# Flight_Controller_board.net
KiCad netlist of a schematic drawn in EAGLE
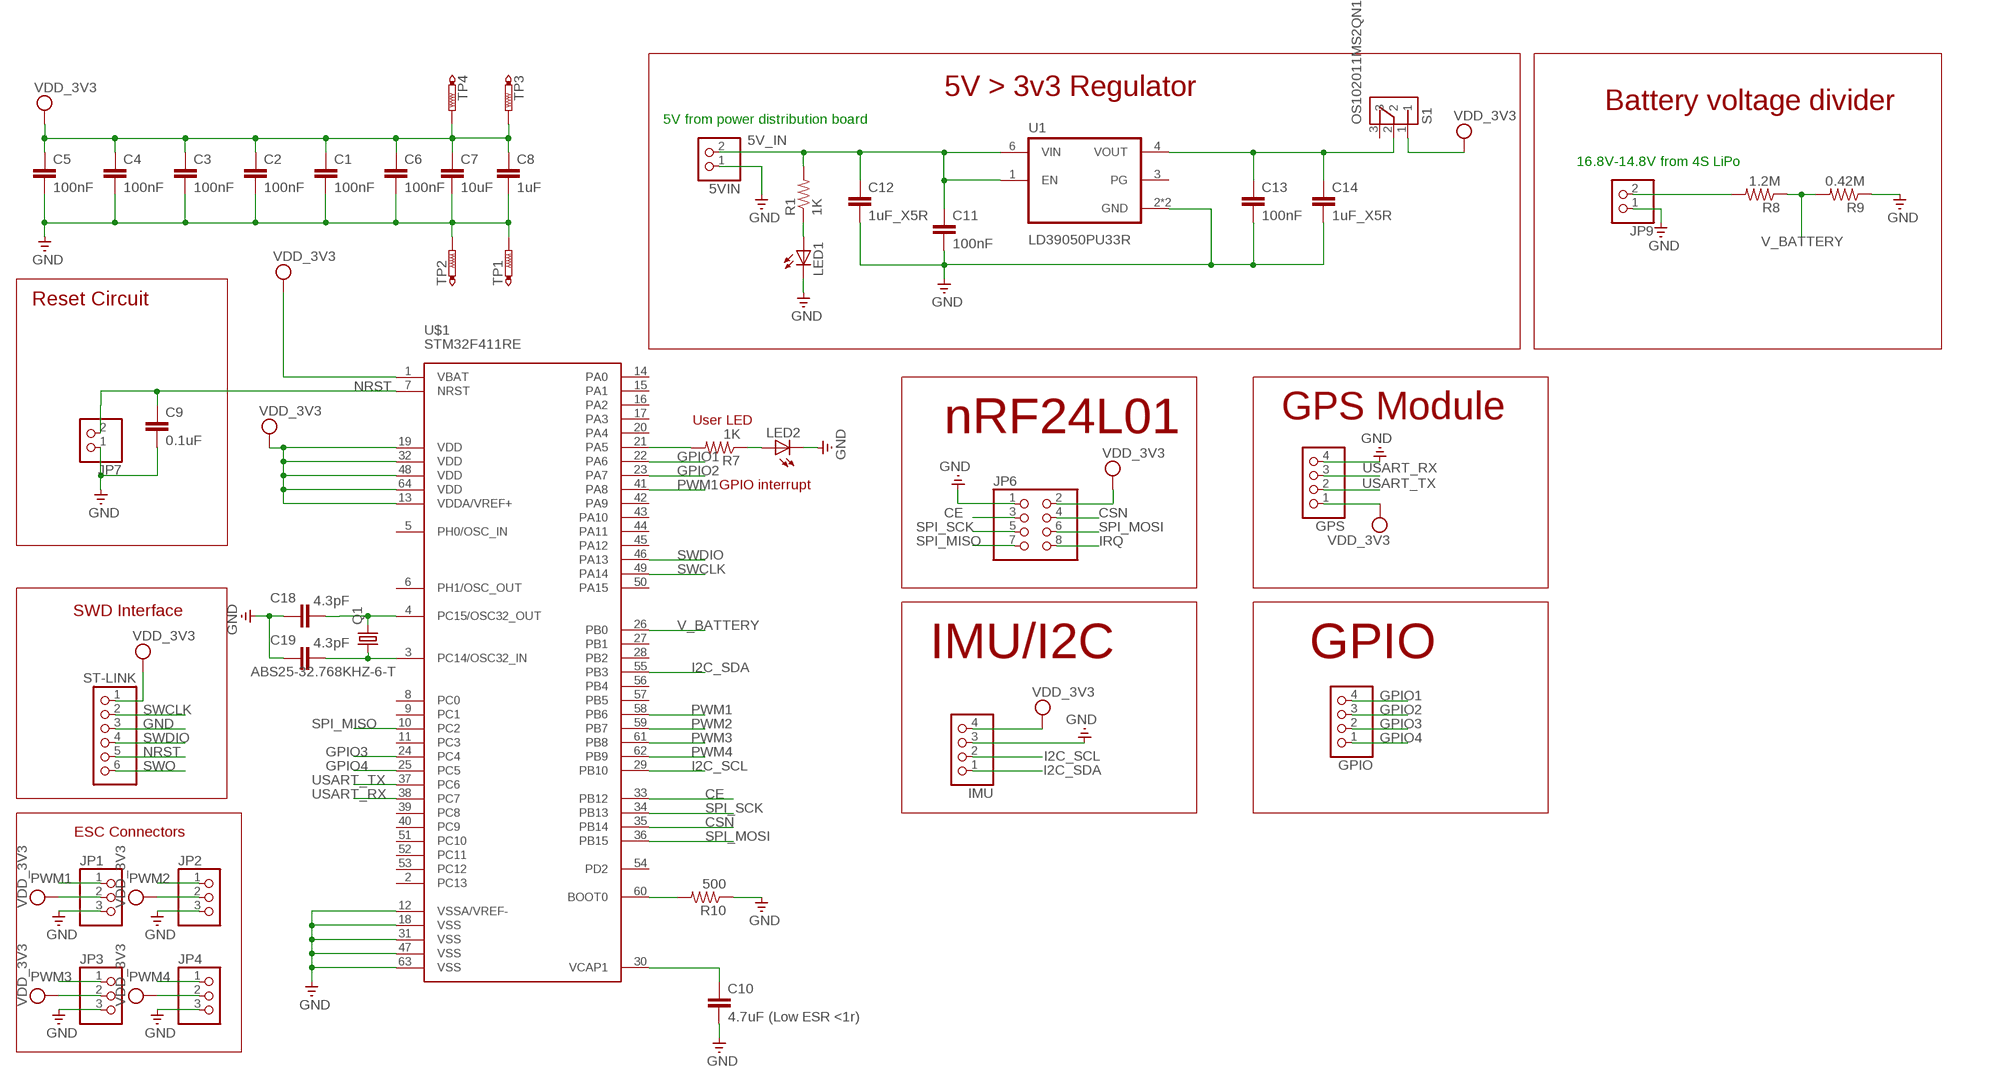
[diagram p0: schematic, sheet 1]

(export (version "E")
  (design (tool "Eeschema 10.0.6"))
  (components
    (comp (ref "5VIN")
      (value "PINHD-1X2")
      (footprint "eagle-import:1X02")
      (libsource (lib "eagle-import") (part "PINHD-1X2"))
    )
    (comp (ref "C1")
      (value "100nF")
      (footprint "eagle-import:0603-CAP")
      (libsource (lib "eagle-import") (part "CAP0603-CAP"))
    )
    (comp (ref "C2")
      (value "100nF")
      (footprint "eagle-import:0603-CAP")
      (libsource (lib "eagle-import") (part "CAP0603-CAP"))
    )
    (comp (ref "C3")
      (value "100nF")
      (footprint "eagle-import:0603-CAP")
      (libsource (lib "eagle-import") (part "CAP0603-CAP"))
    )
    (comp (ref "C4")
      (value "100nF")
      (footprint "eagle-import:0603-CAP")
      (libsource (lib "eagle-import") (part "CAP0603-CAP"))
    )
    (comp (ref "C5")
      (value "100nF")
      (footprint "eagle-import:0603-CAP")
      (libsource (lib "eagle-import") (part "CAP0603-CAP"))
    )
    (comp (ref "C6")
      (value "100nF")
      (footprint "eagle-import:0603-CAP")
      (libsource (lib "eagle-import") (part "CAP0603-CAP"))
    )
    (comp (ref "C7")
      (value "10uF")
      (footprint "eagle-import:0603-CAP")
      (libsource (lib "eagle-import") (part "CAP0603-CAP"))
    )
    (comp (ref "C8")
      (value "1uF")
      (footprint "eagle-import:0603-CAP")
      (libsource (lib "eagle-import") (part "CAP0603-CAP"))
    )
    (comp (ref "C9")
      (value "0.1uF")
      (footprint "eagle-import:0603-CAP")
      (libsource (lib "eagle-import") (part "CAP0603-CAP"))
    )
    (comp (ref "C10")
      (value "4.7uF (Low ESR <1r)")
      (footprint "eagle-import:1210")
      (libsource (lib "eagle-import") (part "CAP1210"))
    )
    (comp (ref "C11")
      (value "100nF")
      (footprint "eagle-import:0603-CAP")
      (libsource (lib "eagle-import") (part "CAP0603-CAP"))
    )
    (comp (ref "C12")
      (value "1uF_X5R")
      (footprint "eagle-import:0603-CAP")
      (libsource (lib "eagle-import") (part "CAP0603-CAP"))
    )
    (comp (ref "C13")
      (value "100nF")
      (footprint "eagle-import:0603-CAP")
      (libsource (lib "eagle-import") (part "CAP0603-CAP"))
    )
    (comp (ref "C14")
      (value "1uF_X5R")
      (footprint "eagle-import:0603-CAP")
      (libsource (lib "eagle-import") (part "CAP0603-CAP"))
    )
    (comp (ref "C18")
      (value "4.3pF")
      (footprint "eagle-import:0603-CAP")
      (libsource (lib "eagle-import") (part "CAP0603-CAP"))
    )
    (comp (ref "C19")
      (value "4.3pF")
      (footprint "eagle-import:0603-CAP")
      (libsource (lib "eagle-import") (part "CAP0603-CAP"))
    )
    (comp (ref "GPIO")
      (value "PINHD-1X4")
      (footprint "eagle-import:1X04")
      (libsource (lib "eagle-import") (part "PINHD-1X4"))
    )
    (comp (ref "GPS")
      (value "PINHD-1X4")
      (footprint "eagle-import:1X04")
      (libsource (lib "eagle-import") (part "PINHD-1X4"))
    )
    (comp (ref "IMU")
      (value "PINHD-1X4")
      (footprint "eagle-import:1X04")
      (libsource (lib "eagle-import") (part "PINHD-1X4"))
    )
    (comp (ref "JP1")
      (value "PINHD-1X3")
      (footprint "eagle-import:1X03")
      (libsource (lib "eagle-import") (part "PINHD-1X3"))
    )
    (comp (ref "JP2")
      (value "PINHD-1X3")
      (footprint "eagle-import:1X03")
      (libsource (lib "eagle-import") (part "PINHD-1X3"))
    )
    (comp (ref "JP3")
      (value "PINHD-1X3")
      (footprint "eagle-import:1X03")
      (libsource (lib "eagle-import") (part "PINHD-1X3"))
    )
    (comp (ref "JP4")
      (value "PINHD-1X3")
      (footprint "eagle-import:1X03")
      (libsource (lib "eagle-import") (part "PINHD-1X3"))
    )
    (comp (ref "JP6")
      (value "PINHD-2X4")
      (footprint "eagle-import:2X04")
      (libsource (lib "eagle-import") (part "PINHD-2X4"))
    )
    (comp (ref "JP7")
      (value "PINHD-1X2")
      (footprint "eagle-import:1X02")
      (libsource (lib "eagle-import") (part "PINHD-1X2"))
    )
    (comp (ref "JP9")
      (value "PINHD-1X2")
      (footprint "eagle-import:1X02")
      (libsource (lib "eagle-import") (part "PINHD-1X2"))
    )
    (comp (ref "LED1")
      (value "LEDCHIPLED_0603")
      (footprint "eagle-import:CHIPLED_0603")
      (libsource (lib "eagle-import") (part "LEDCHIPLED_0603"))
    )
    (comp (ref "LED2")
      (value "LEDCHIPLED_0603")
      (footprint "eagle-import:CHIPLED_0603")
      (libsource (lib "eagle-import") (part "LEDCHIPLED_0603"))
    )
    (comp (ref "Q1")
      (value "ABS25-32.768KHZ-6-T")
      (footprint "eagle-import:MC-306")
      (fields (field (name "MPN") "MC-306 60.0KHZ  100PPM ,12.5PF"))
      (libsource (lib "eagle-import") (part "MC-306"))
    )
    (comp (ref "R1")
      (value "1K")
      (footprint "eagle-import:0603-RES")
      (libsource (lib "eagle-import") (part "RESISTOR0603-RES"))
    )
    (comp (ref "R7")
      (value "1K")
      (footprint "eagle-import:0603-RES")
      (libsource (lib "eagle-import") (part "RESISTOR0603-RES"))
    )
    (comp (ref "R8")
      (value "1.2M")
      (footprint "eagle-import:0603-RES")
      (libsource (lib "eagle-import") (part "RESISTOR0603-RES"))
    )
    (comp (ref "R9")
      (value "0.42M")
      (footprint "eagle-import:0603-RES")
      (libsource (lib "eagle-import") (part "RESISTOR0603-RES"))
    )
    (comp (ref "R10")
      (value "500")
      (footprint "eagle-import:0603-RES")
      (libsource (lib "eagle-import") (part "RESISTOR0603-RES"))
    )
    (comp (ref "S1")
      (value "OS102011MS2QN1")
      (footprint "eagle-import:SW_OS102011MS2QN1")
      (fields (field (name "MF") "C&K"))
      (libsource (lib "eagle-import") (part "OS102011MS2QN1"))
    )
    (comp (ref "ST-LINK")
      (value "PINHD-1X6")
      (footprint "eagle-import:1X06")
      (libsource (lib "eagle-import") (part "PINHD-1X6"))
    )
    (comp (ref "TP1")
      (value "PTR1B1,27")
      (footprint "eagle-import:B1,27")
      (libsource (lib "eagle-import") (part "PTR1B1,27"))
    )
    (comp (ref "TP2")
      (value "PTR1B1,27")
      (footprint "eagle-import:B1,27")
      (libsource (lib "eagle-import") (part "PTR1B1,27"))
    )
    (comp (ref "TP3")
      (value "PTR1B1,27")
      (footprint "eagle-import:B1,27")
      (libsource (lib "eagle-import") (part "PTR1B1,27"))
    )
    (comp (ref "TP4")
      (value "PTR1B1,27")
      (footprint "eagle-import:B1,27")
      (libsource (lib "eagle-import") (part "PTR1B1,27"))
    )
    (comp (ref "U$1")
      (value "STM32F411RE")
      (footprint "eagle-import:LQFP64")
      (libsource (lib "eagle-import") (part "STM32F411XC"))
    )
    (comp (ref "U1")
      (value "LD39050PU33R")
      (footprint "eagle-import:SON95P300X300X100-7N")
      (fields (field (name "MF") "STMicroelectronics"))
      (libsource (lib "eagle-import") (part "LD39050PU33R"))
    )
  )
  (nets
    (net (code "1") (name "/5V_IN") (class "Default")
      (node (ref "5VIN") (pin "2") (pinfunction "2_2") (pintype "passive"))
      (node (ref "C11") (pin "1") (pinfunction "1_1") (pintype "passive"))
      (node (ref "C12") (pin "1") (pinfunction "1_1") (pintype "passive"))
      (node (ref "R1") (pin "2") (pinfunction "2_2") (pintype "passive"))
      (node (ref "U1") (pin "1") (pinfunction "EN_1") (pintype "input"))
      (node (ref "U1") (pin "6") (pinfunction "VIN_6") (pintype "power_in"))
    )
    (net (code "2") (name "/CE") (class "Default")
      (node (ref "JP6") (pin "3") (pinfunction "3_3") (pintype "passive"))
      (node (ref "U$1") (pin "33") (pinfunction "PB12_33") (pintype "bidirectional"))
    )
    (net (code "3") (name "/CSN") (class "Default")
      (node (ref "JP6") (pin "4") (pinfunction "4_4") (pintype "passive"))
      (node (ref "U$1") (pin "35") (pinfunction "PB14_35") (pintype "bidirectional"))
    )
    (net (code "4") (name "/GPIO1") (class "Default")
      (node (ref "GPIO") (pin "4") (pinfunction "4_4") (pintype "passive"))
      (node (ref "U$1") (pin "22") (pinfunction "PA6_22") (pintype "bidirectional"))
    )
    (net (code "5") (name "/GPIO2") (class "Default")
      (node (ref "GPIO") (pin "3") (pinfunction "3_3") (pintype "passive"))
      (node (ref "U$1") (pin "23") (pinfunction "PA7_23") (pintype "bidirectional"))
    )
    (net (code "6") (name "/GPIO3") (class "Default")
      (node (ref "GPIO") (pin "2") (pinfunction "2_2") (pintype "passive"))
      (node (ref "U$1") (pin "24") (pinfunction "PC4_24") (pintype "bidirectional"))
    )
    (net (code "7") (name "/GPIO4") (class "Default")
      (node (ref "GPIO") (pin "1") (pinfunction "1_1") (pintype "passive"))
      (node (ref "U$1") (pin "25") (pinfunction "PC5_25") (pintype "bidirectional"))
    )
    (net (code "8") (name "/I2C_SCL") (class "Default")
      (node (ref "IMU") (pin "2") (pinfunction "2_2") (pintype "passive"))
      (node (ref "U$1") (pin "29") (pinfunction "PB10_29") (pintype "bidirectional"))
    )
    (net (code "9") (name "/I2C_SDA") (class "Default")
      (node (ref "IMU") (pin "1") (pinfunction "1_1") (pintype "passive"))
      (node (ref "U$1") (pin "55") (pinfunction "PB3_55") (pintype "bidirectional"))
    )
    (net (code "10") (name "/IRQ") (class "Default")
      (node (ref "JP6") (pin "8") (pinfunction "8_8") (pintype "passive"))
    )
    (net (code "11") (name "/NRST") (class "Default")
      (node (ref "C9") (pin "1") (pinfunction "1_1") (pintype "passive"))
      (node (ref "JP7") (pin "2") (pinfunction "2_2") (pintype "passive"))
      (node (ref "ST-LINK") (pin "5") (pinfunction "5_5") (pintype "passive"))
      (node (ref "U$1") (pin "7") (pinfunction "NRST_7") (pintype "bidirectional"))
    )
    (net (code "12") (name "/PWM1") (class "Default")
      (node (ref "JP1") (pin "1") (pinfunction "1_1") (pintype "passive"))
      (node (ref "U$1") (pin "41") (pinfunction "PA8_41") (pintype "bidirectional"))
      (node (ref "U$1") (pin "58") (pinfunction "PB6_58") (pintype "bidirectional"))
    )
    (net (code "13") (name "/PWM2") (class "Default")
      (node (ref "JP2") (pin "1") (pinfunction "1_1") (pintype "passive"))
      (node (ref "U$1") (pin "59") (pinfunction "PB7_59") (pintype "bidirectional"))
    )
    (net (code "14") (name "/PWM3") (class "Default")
      (node (ref "JP3") (pin "1") (pinfunction "1_1") (pintype "passive"))
      (node (ref "U$1") (pin "61") (pinfunction "PB8_61") (pintype "bidirectional"))
    )
    (net (code "15") (name "/PWM4") (class "Default")
      (node (ref "JP4") (pin "1") (pinfunction "1_1") (pintype "passive"))
      (node (ref "U$1") (pin "62") (pinfunction "PB9_62") (pintype "bidirectional"))
    )
    (net (code "16") (name "/SPI_MISO") (class "Default")
      (node (ref "JP6") (pin "7") (pinfunction "7_7") (pintype "passive"))
      (node (ref "U$1") (pin "10") (pinfunction "PC2_10") (pintype "bidirectional"))
    )
    (net (code "17") (name "/SPI_MOSI") (class "Default")
      (node (ref "JP6") (pin "6") (pinfunction "6_6") (pintype "passive"))
      (node (ref "U$1") (pin "36") (pinfunction "PB15_36") (pintype "bidirectional"))
    )
    (net (code "18") (name "/SPI_SCK") (class "Default")
      (node (ref "JP6") (pin "5") (pinfunction "5_5") (pintype "passive"))
      (node (ref "U$1") (pin "34") (pinfunction "PB13_34") (pintype "bidirectional"))
    )
    (net (code "19") (name "/SWCLK") (class "Default")
      (node (ref "ST-LINK") (pin "2") (pinfunction "2_2") (pintype "passive"))
      (node (ref "U$1") (pin "49") (pinfunction "PA14_49") (pintype "bidirectional"))
    )
    (net (code "20") (name "/SWDIO") (class "Default")
      (node (ref "ST-LINK") (pin "4") (pinfunction "4_4") (pintype "passive"))
      (node (ref "U$1") (pin "46") (pinfunction "PA13_46") (pintype "bidirectional"))
    )
    (net (code "21") (name "/SWO") (class "Default")
      (node (ref "ST-LINK") (pin "6") (pinfunction "6_6") (pintype "passive"))
    )
    (net (code "22") (name "/USART_RX") (class "Default")
      (node (ref "GPS") (pin "3") (pinfunction "3_3") (pintype "passive"))
      (node (ref "U$1") (pin "38") (pinfunction "PC7_38") (pintype "bidirectional"))
    )
    (net (code "23") (name "/USART_TX") (class "Default")
      (node (ref "GPS") (pin "2") (pinfunction "2_2") (pintype "passive"))
      (node (ref "U$1") (pin "37") (pinfunction "PC6_37") (pintype "bidirectional"))
    )
    (net (code "24") (name "/V_BATTERY") (class "Default")
      (node (ref "R8") (pin "1") (pinfunction "1_1") (pintype "passive"))
      (node (ref "R9") (pin "2") (pinfunction "2_2") (pintype "passive"))
      (node (ref "U$1") (pin "26") (pinfunction "PB0_26") (pintype "bidirectional"))
    )
    (net (code "25") (name "GND") (class "Default")
      (node (ref "5VIN") (pin "1") (pinfunction "1_1") (pintype "passive"))
      (node (ref "C1") (pin "2") (pinfunction "2_2") (pintype "passive"))
      (node (ref "C10") (pin "2") (pinfunction "2_2") (pintype "passive"))
      (node (ref "C11") (pin "2") (pinfunction "2_2") (pintype "passive"))
      (node (ref "C12") (pin "2") (pinfunction "2_2") (pintype "passive"))
      (node (ref "C13") (pin "2") (pinfunction "2_2") (pintype "passive"))
      (node (ref "C14") (pin "2") (pinfunction "2_2") (pintype "passive"))
      (node (ref "C18") (pin "1") (pinfunction "1_1") (pintype "passive"))
      (node (ref "C19") (pin "1") (pinfunction "1_1") (pintype "passive"))
      (node (ref "C2") (pin "2") (pinfunction "2_2") (pintype "passive"))
      (node (ref "C3") (pin "2") (pinfunction "2_2") (pintype "passive"))
      (node (ref "C4") (pin "2") (pinfunction "2_2") (pintype "passive"))
      (node (ref "C5") (pin "2") (pinfunction "2_2") (pintype "passive"))
      (node (ref "C6") (pin "2") (pinfunction "2_2") (pintype "passive"))
      (node (ref "C7") (pin "2") (pinfunction "2_2") (pintype "passive"))
      (node (ref "C8") (pin "2") (pinfunction "2_2") (pintype "passive"))
      (node (ref "C9") (pin "2") (pinfunction "2_2") (pintype "passive"))
      (node (ref "GPS") (pin "4") (pinfunction "4_4") (pintype "passive"))
      (node (ref "IMU") (pin "3") (pinfunction "3_3") (pintype "passive"))
      (node (ref "JP1") (pin "3") (pinfunction "3_3") (pintype "passive"))
      (node (ref "JP2") (pin "3") (pinfunction "3_3") (pintype "passive"))
      (node (ref "JP3") (pin "3") (pinfunction "3_3") (pintype "passive"))
      (node (ref "JP4") (pin "3") (pinfunction "3_3") (pintype "passive"))
      (node (ref "JP6") (pin "1") (pinfunction "1_1") (pintype "passive"))
      (node (ref "JP7") (pin "1") (pinfunction "1_1") (pintype "passive"))
      (node (ref "JP9") (pin "1") (pinfunction "1_1") (pintype "passive"))
      (node (ref "LED1") (pin "C") (pinfunction "C_C") (pintype "passive"))
      (node (ref "LED2") (pin "C") (pinfunction "C_C") (pintype "passive"))
      (node (ref "R10") (pin "1") (pinfunction "1_1") (pintype "passive"))
      (node (ref "R9") (pin "1") (pinfunction "1_1") (pintype "passive"))
      (node (ref "ST-LINK") (pin "3") (pinfunction "3_3") (pintype "passive"))
      (node (ref "TP1") (pin "TP") (pinfunction "TP_TP") (pintype "input"))
      (node (ref "TP2") (pin "TP") (pinfunction "TP_TP") (pintype "input"))
      (node (ref "U$1") (pin "12") (pinfunction "VSSA/VREF-_12") (pintype "bidirectional"))
      (node (ref "U$1") (pin "18") (pinfunction "VSS_18") (pintype "bidirectional"))
      (node (ref "U$1") (pin "31") (pinfunction "VSS_31") (pintype "bidirectional"))
      (node (ref "U$1") (pin "47") (pinfunction "VSS_47") (pintype "bidirectional"))
      (node (ref "U$1") (pin "63") (pinfunction "VSS_63") (pintype "bidirectional"))
      (node (ref "U1") (pin "2") (pinfunction "GND_2") (pintype "power_in"))
      (node (ref "U1") (pin "7") (pinfunction "GND_7") (pintype "power_in"))
    )
    (net (code "26") (name "Net-(JP9-Pad2)") (class "Default")
      (node (ref "JP9") (pin "2") (pinfunction "2_2") (pintype "passive"))
      (node (ref "R8") (pin "2") (pinfunction "2_2") (pintype "passive"))
    )
    (net (code "27") (name "Net-(LED1-PadA)") (class "Default")
      (node (ref "LED1") (pin "A") (pinfunction "A_A") (pintype "passive"))
      (node (ref "R1") (pin "1") (pinfunction "1_1") (pintype "passive"))
    )
    (net (code "28") (name "Net-(LED2-PadA)") (class "Default")
      (node (ref "LED2") (pin "A") (pinfunction "A_A") (pintype "passive"))
      (node (ref "R7") (pin "1") (pinfunction "1_1") (pintype "passive"))
    )
    (net (code "29") (name "Net-(Q1-2)") (class "Default")
      (node (ref "C18") (pin "2") (pinfunction "2_2") (pintype "passive"))
      (node (ref "Q1") (pin "4") (pinfunction "2_4") (pintype "passive"))
      (node (ref "U$1") (pin "4") (pinfunction "PC15/OSC32_OUT_4") (pintype "bidirectional"))
    )
    (net (code "30") (name "Net-(U$1-BOOT0)") (class "Default")
      (node (ref "R10") (pin "2") (pinfunction "2_2") (pintype "passive"))
      (node (ref "U$1") (pin "60") (pinfunction "BOOT0_60") (pintype "bidirectional"))
    )
    (net (code "31") (name "Net-(U$1-PA5)") (class "Default")
      (node (ref "R7") (pin "2") (pinfunction "2_2") (pintype "passive"))
      (node (ref "U$1") (pin "21") (pinfunction "PA5_21") (pintype "bidirectional"))
    )
    (net (code "32") (name "Net-(U$1-PC14{slash}OSC32_IN)") (class "Default")
      (node (ref "C19") (pin "2") (pinfunction "2_2") (pintype "passive"))
      (node (ref "Q1") (pin "1") (pinfunction "1_1") (pintype "passive"))
      (node (ref "U$1") (pin "3") (pinfunction "PC14/OSC32_IN_3") (pintype "bidirectional"))
    )
    (net (code "33") (name "Net-(U$1-VCAP1)") (class "Default")
      (node (ref "C10") (pin "1") (pinfunction "1_1") (pintype "passive"))
      (node (ref "U$1") (pin "30") (pinfunction "VCAP1_30") (pintype "bidirectional"))
    )
    (net (code "34") (name "Net-(U1-VOUT)") (class "Default")
      (node (ref "C13") (pin "1") (pinfunction "1_1") (pintype "passive"))
      (node (ref "C14") (pin "1") (pinfunction "1_1") (pintype "passive"))
      (node (ref "S1") (pin "2") (pinfunction "2_2") (pintype "passive"))
      (node (ref "U1") (pin "4") (pinfunction "VOUT_4") (pintype "output"))
    )
    (net (code "35") (name "VDD_3V3") (class "Default")
      (node (ref "C1") (pin "1") (pinfunction "1_1") (pintype "passive"))
      (node (ref "C2") (pin "1") (pinfunction "1_1") (pintype "passive"))
      (node (ref "C3") (pin "1") (pinfunction "1_1") (pintype "passive"))
      (node (ref "C4") (pin "1") (pinfunction "1_1") (pintype "passive"))
      (node (ref "C5") (pin "1") (pinfunction "1_1") (pintype "passive"))
      (node (ref "C6") (pin "1") (pinfunction "1_1") (pintype "passive"))
      (node (ref "C7") (pin "1") (pinfunction "1_1") (pintype "passive"))
      (node (ref "C8") (pin "1") (pinfunction "1_1") (pintype "passive"))
      (node (ref "GPS") (pin "1") (pinfunction "1_1") (pintype "passive"))
      (node (ref "IMU") (pin "4") (pinfunction "4_4") (pintype "passive"))
      (node (ref "JP1") (pin "2") (pinfunction "2_2") (pintype "passive"))
      (node (ref "JP2") (pin "2") (pinfunction "2_2") (pintype "passive"))
      (node (ref "JP3") (pin "2") (pinfunction "2_2") (pintype "passive"))
      (node (ref "JP4") (pin "2") (pinfunction "2_2") (pintype "passive"))
      (node (ref "JP6") (pin "2") (pinfunction "2_2") (pintype "passive"))
      (node (ref "S1") (pin "1") (pinfunction "1_1") (pintype "passive"))
      (node (ref "ST-LINK") (pin "1") (pinfunction "1_1") (pintype "passive"))
      (node (ref "TP3") (pin "TP") (pinfunction "TP_TP") (pintype "input"))
      (node (ref "TP4") (pin "TP") (pinfunction "TP_TP") (pintype "input"))
      (node (ref "U$1") (pin "1") (pinfunction "VBAT_1") (pintype "bidirectional"))
      (node (ref "U$1") (pin "13") (pinfunction "VDDA/VREF+_13") (pintype "bidirectional"))
      (node (ref "U$1") (pin "19") (pinfunction "VDD_19") (pintype "bidirectional"))
      (node (ref "U$1") (pin "32") (pinfunction "VDD_32") (pintype "bidirectional"))
      (node (ref "U$1") (pin "48") (pinfunction "VDD_48") (pintype "bidirectional"))
      (node (ref "U$1") (pin "64") (pinfunction "VDD_64") (pintype "bidirectional"))
    )
    (net (code "36") (name "unconnected-(S1-Pad3)") (class "Default")
      (node (ref "S1") (pin "3") (pinfunction "3_3") (pintype "passive"))
    )
    (net (code "37") (name "unconnected-(U$1-PA0-Pad14)") (class "Default")
      (node (ref "U$1") (pin "14") (pinfunction "PA0_14") (pintype "bidirectional"))
    )
    (net (code "38") (name "unconnected-(U$1-PA1-Pad15)") (class "Default")
      (node (ref "U$1") (pin "15") (pinfunction "PA1_15") (pintype "bidirectional"))
    )
    (net (code "39") (name "unconnected-(U$1-PA2-Pad16)") (class "Default")
      (node (ref "U$1") (pin "16") (pinfunction "PA2_16") (pintype "bidirectional"))
    )
    (net (code "40") (name "unconnected-(U$1-PA3-Pad17)") (class "Default")
      (node (ref "U$1") (pin "17") (pinfunction "PA3_17") (pintype "bidirectional"))
    )
    (net (code "41") (name "unconnected-(U$1-PA4-Pad20)") (class "Default")
      (node (ref "U$1") (pin "20") (pinfunction "PA4_20") (pintype "bidirectional"))
    )
    (net (code "42") (name "unconnected-(U$1-PA9-Pad42)") (class "Default")
      (node (ref "U$1") (pin "42") (pinfunction "PA9_42") (pintype "bidirectional"))
    )
    (net (code "43") (name "unconnected-(U$1-PA10-Pad43)") (class "Default")
      (node (ref "U$1") (pin "43") (pinfunction "PA10_43") (pintype "bidirectional"))
    )
    (net (code "44") (name "unconnected-(U$1-PA11-Pad44)") (class "Default")
      (node (ref "U$1") (pin "44") (pinfunction "PA11_44") (pintype "bidirectional"))
    )
    (net (code "45") (name "unconnected-(U$1-PA12-Pad45)") (class "Default")
      (node (ref "U$1") (pin "45") (pinfunction "PA12_45") (pintype "bidirectional"))
    )
    (net (code "46") (name "unconnected-(U$1-PA15-Pad50)") (class "Default")
      (node (ref "U$1") (pin "50") (pinfunction "PA15_50") (pintype "bidirectional"))
    )
    (net (code "47") (name "unconnected-(U$1-PB1-Pad27)") (class "Default")
      (node (ref "U$1") (pin "27") (pinfunction "PB1_27") (pintype "bidirectional"))
    )
    (net (code "48") (name "unconnected-(U$1-PB2-Pad28)") (class "Default")
      (node (ref "U$1") (pin "28") (pinfunction "PB2_28") (pintype "bidirectional"))
    )
    (net (code "49") (name "unconnected-(U$1-PB4-Pad56)") (class "Default")
      (node (ref "U$1") (pin "56") (pinfunction "PB4_56") (pintype "bidirectional"))
    )
    (net (code "50") (name "unconnected-(U$1-PB5-Pad57)") (class "Default")
      (node (ref "U$1") (pin "57") (pinfunction "PB5_57") (pintype "bidirectional"))
    )
    (net (code "51") (name "unconnected-(U$1-PC0-Pad8)") (class "Default")
      (node (ref "U$1") (pin "8") (pinfunction "PC0_8") (pintype "bidirectional"))
    )
    (net (code "52") (name "unconnected-(U$1-PC1-Pad9)") (class "Default")
      (node (ref "U$1") (pin "9") (pinfunction "PC1_9") (pintype "bidirectional"))
    )
    (net (code "53") (name "unconnected-(U$1-PC3-Pad11)") (class "Default")
      (node (ref "U$1") (pin "11") (pinfunction "PC3_11") (pintype "bidirectional"))
    )
    (net (code "54") (name "unconnected-(U$1-PC8-Pad39)") (class "Default")
      (node (ref "U$1") (pin "39") (pinfunction "PC8_39") (pintype "bidirectional"))
    )
    (net (code "55") (name "unconnected-(U$1-PC9-Pad40)") (class "Default")
      (node (ref "U$1") (pin "40") (pinfunction "PC9_40") (pintype "bidirectional"))
    )
    (net (code "56") (name "unconnected-(U$1-PC10-Pad51)") (class "Default")
      (node (ref "U$1") (pin "51") (pinfunction "PC10_51") (pintype "bidirectional"))
    )
    (net (code "57") (name "unconnected-(U$1-PC11-Pad52)") (class "Default")
      (node (ref "U$1") (pin "52") (pinfunction "PC11_52") (pintype "bidirectional"))
    )
    (net (code "58") (name "unconnected-(U$1-PC12-Pad53)") (class "Default")
      (node (ref "U$1") (pin "53") (pinfunction "PC12_53") (pintype "bidirectional"))
    )
    (net (code "59") (name "unconnected-(U$1-PC13-Pad2)") (class "Default")
      (node (ref "U$1") (pin "2") (pinfunction "PC13_2") (pintype "bidirectional"))
    )
    (net (code "60") (name "unconnected-(U$1-PD2-Pad54)") (class "Default")
      (node (ref "U$1") (pin "54") (pinfunction "PD2_54") (pintype "bidirectional"))
    )
    (net (code "61") (name "unconnected-(U$1-PH0{slash}OSC_IN-Pad5)") (class "Default")
      (node (ref "U$1") (pin "5") (pinfunction "PH0/OSC_IN_5") (pintype "bidirectional"))
    )
    (net (code "62") (name "unconnected-(U$1-PH1{slash}OSC_OUT-Pad6)") (class "Default")
      (node (ref "U$1") (pin "6") (pinfunction "PH1/OSC_OUT_6") (pintype "bidirectional"))
    )
    (net (code "63") (name "unconnected-(U1-PG-Pad3)") (class "Default")
      (node (ref "U1") (pin "3") (pinfunction "PG_3") (pintype "bidirectional"))
    )
  )
)
